# Battery.net
KiCad netlist of a schematic drawn in Altium Designer
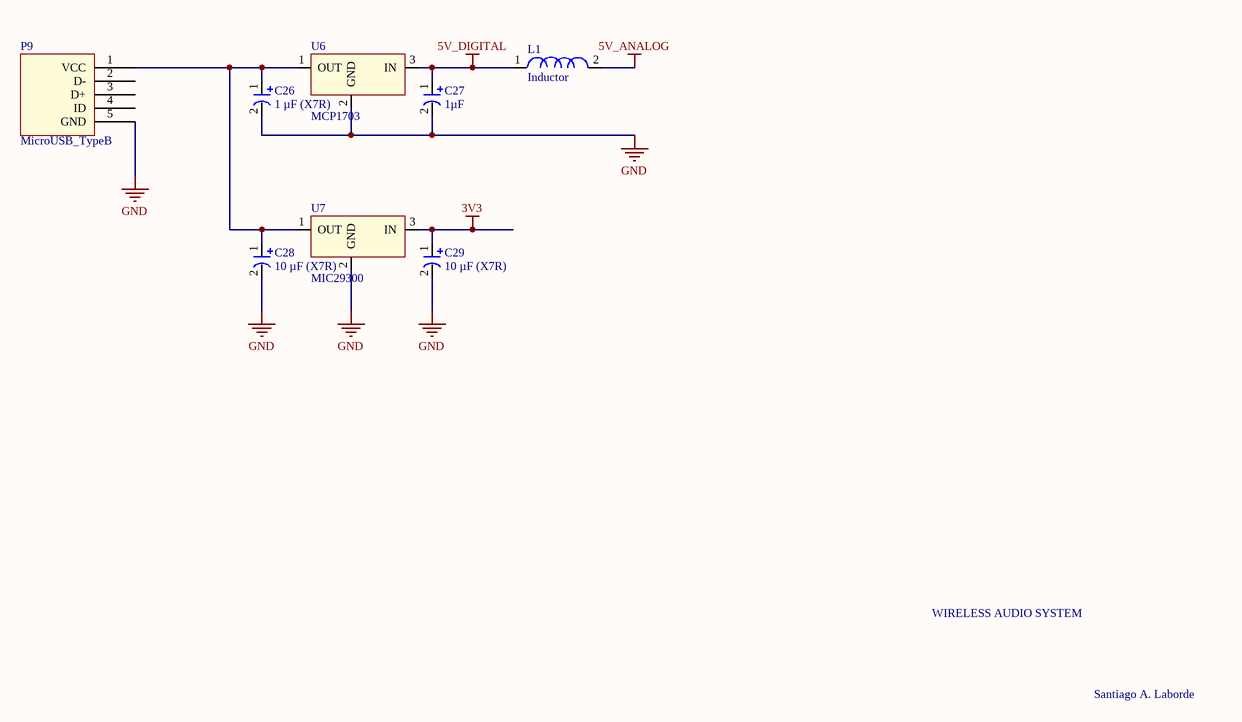
[diagram p0: Battery.SchDoc]

(export (version "E")
  (design (tool "Eeschema 10.0.6"))
  (components
    (comp (ref "C26")
      (value "1 µF (X7R)")
      (footprint "RAD-0.1")
      (description "Polarysed Capacitor")
      (libsource (lib "TD2_Project") (part "Capacitor_Pol"))
    )
    (comp (ref "C27")
      (value "1µF")
      (footprint "RAD-0.1")
      (description "Polarysed Capacitor")
      (libsource (lib "TD2_Project") (part "Capacitor_Pol"))
    )
    (comp (ref "C28")
      (value "10 µF (X7R)")
      (footprint "RAD-0.1")
      (description "Polarysed Capacitor")
      (libsource (lib "TD2_Project") (part "Capacitor_Pol"))
    )
    (comp (ref "C29")
      (value "10 µF (X7R)")
      (footprint "RAD-0.1")
      (description "Polarysed Capacitor")
      (libsource (lib "TD2_Project") (part "Capacitor_Pol"))
    )
    (comp (ref "L1")
      (value "Inductor")
      (footprint "R_0805")
      (libsource (lib "TD2_Project") (part "Inductor"))
    )
    (comp (ref "P9")
      (value "MicroUSB_TypeB")
      (footprint "*TE_2013499-1")
      (libsource (lib "TD2_Project") (part "MicroUSB_TypeB"))
    )
    (comp (ref "U6")
      (value "MCP1703")
      (footprint "SOT-223-3")
      (libsource (lib "TD2_Project") (part "MCP1703"))
    )
    (comp (ref "U7")
      (value "MIC29300")
      (footprint "TO-263-3")
      (libsource (lib "TD2_Project") (part "MIC29300"))
    )
  )
  (nets
    (net (code "1") (name "3V3") (class "Default")
      (node (ref "C29") (pin "1") (pintype "passive"))
      (node (ref "U7") (pin "3") (pinfunction "IN_3") (pintype "passive"))
    )
    (net (code "2") (name "5V_ANALOG") (class "Default") (node (ref "L1") (pin "2") (pintype "passive")))
    (net (code "3") (name "5V_DIGITAL") (class "Default")
      (node (ref "C27") (pin "1") (pintype "passive"))
      (node (ref "L1") (pin "1") (pintype "passive"))
      (node (ref "U6") (pin "3") (pinfunction "IN_3") (pintype "passive"))
    )
    (net (code "4") (name "GND") (class "Default")
      (node (ref "C26") (pin "2") (pintype "passive"))
      (node (ref "C27") (pin "2") (pintype "passive"))
      (node (ref "C28") (pin "2") (pintype "passive"))
      (node (ref "C29") (pin "2") (pintype "passive"))
      (node (ref "P9") (pin "5") (pinfunction "GND_5") (pintype "passive"))
      (node (ref "U6") (pin "2") (pinfunction "GND_2") (pintype "passive"))
      (node (ref "U7") (pin "2") (pinfunction "GND_2") (pintype "passive"))
    )
    (net (code "5") (name "Net-(P9-VCC)") (class "Default")
      (node (ref "C26") (pin "1") (pintype "passive"))
      (node (ref "C28") (pin "1") (pintype "passive"))
      (node (ref "P9") (pin "1") (pinfunction "VCC_1") (pintype "passive"))
      (node (ref "U6") (pin "1") (pinfunction "OUT_1") (pintype "passive"))
      (node (ref "U7") (pin "1") (pinfunction "OUT_1") (pintype "passive"))
    )
    (net (code "6") (name "unconnected-(P9-D+-Pad3)") (class "Default")
      (node (ref "P9") (pin "3") (pinfunction "D+_3") (pintype "passive"))
    )
    (net (code "7") (name "unconnected-(P9-D--Pad2)") (class "Default")
      (node (ref "P9") (pin "2") (pinfunction "D-_2") (pintype "passive"))
    )
    (net (code "8") (name "unconnected-(P9-ID-Pad4)") (class "Default")
      (node (ref "P9") (pin "4") (pinfunction "ID_4") (pintype "passive"))
    )
  )
)
